# Atomwide_TwinMEMC.net
KiCad netlist of a schematic drawn in Altium Designer
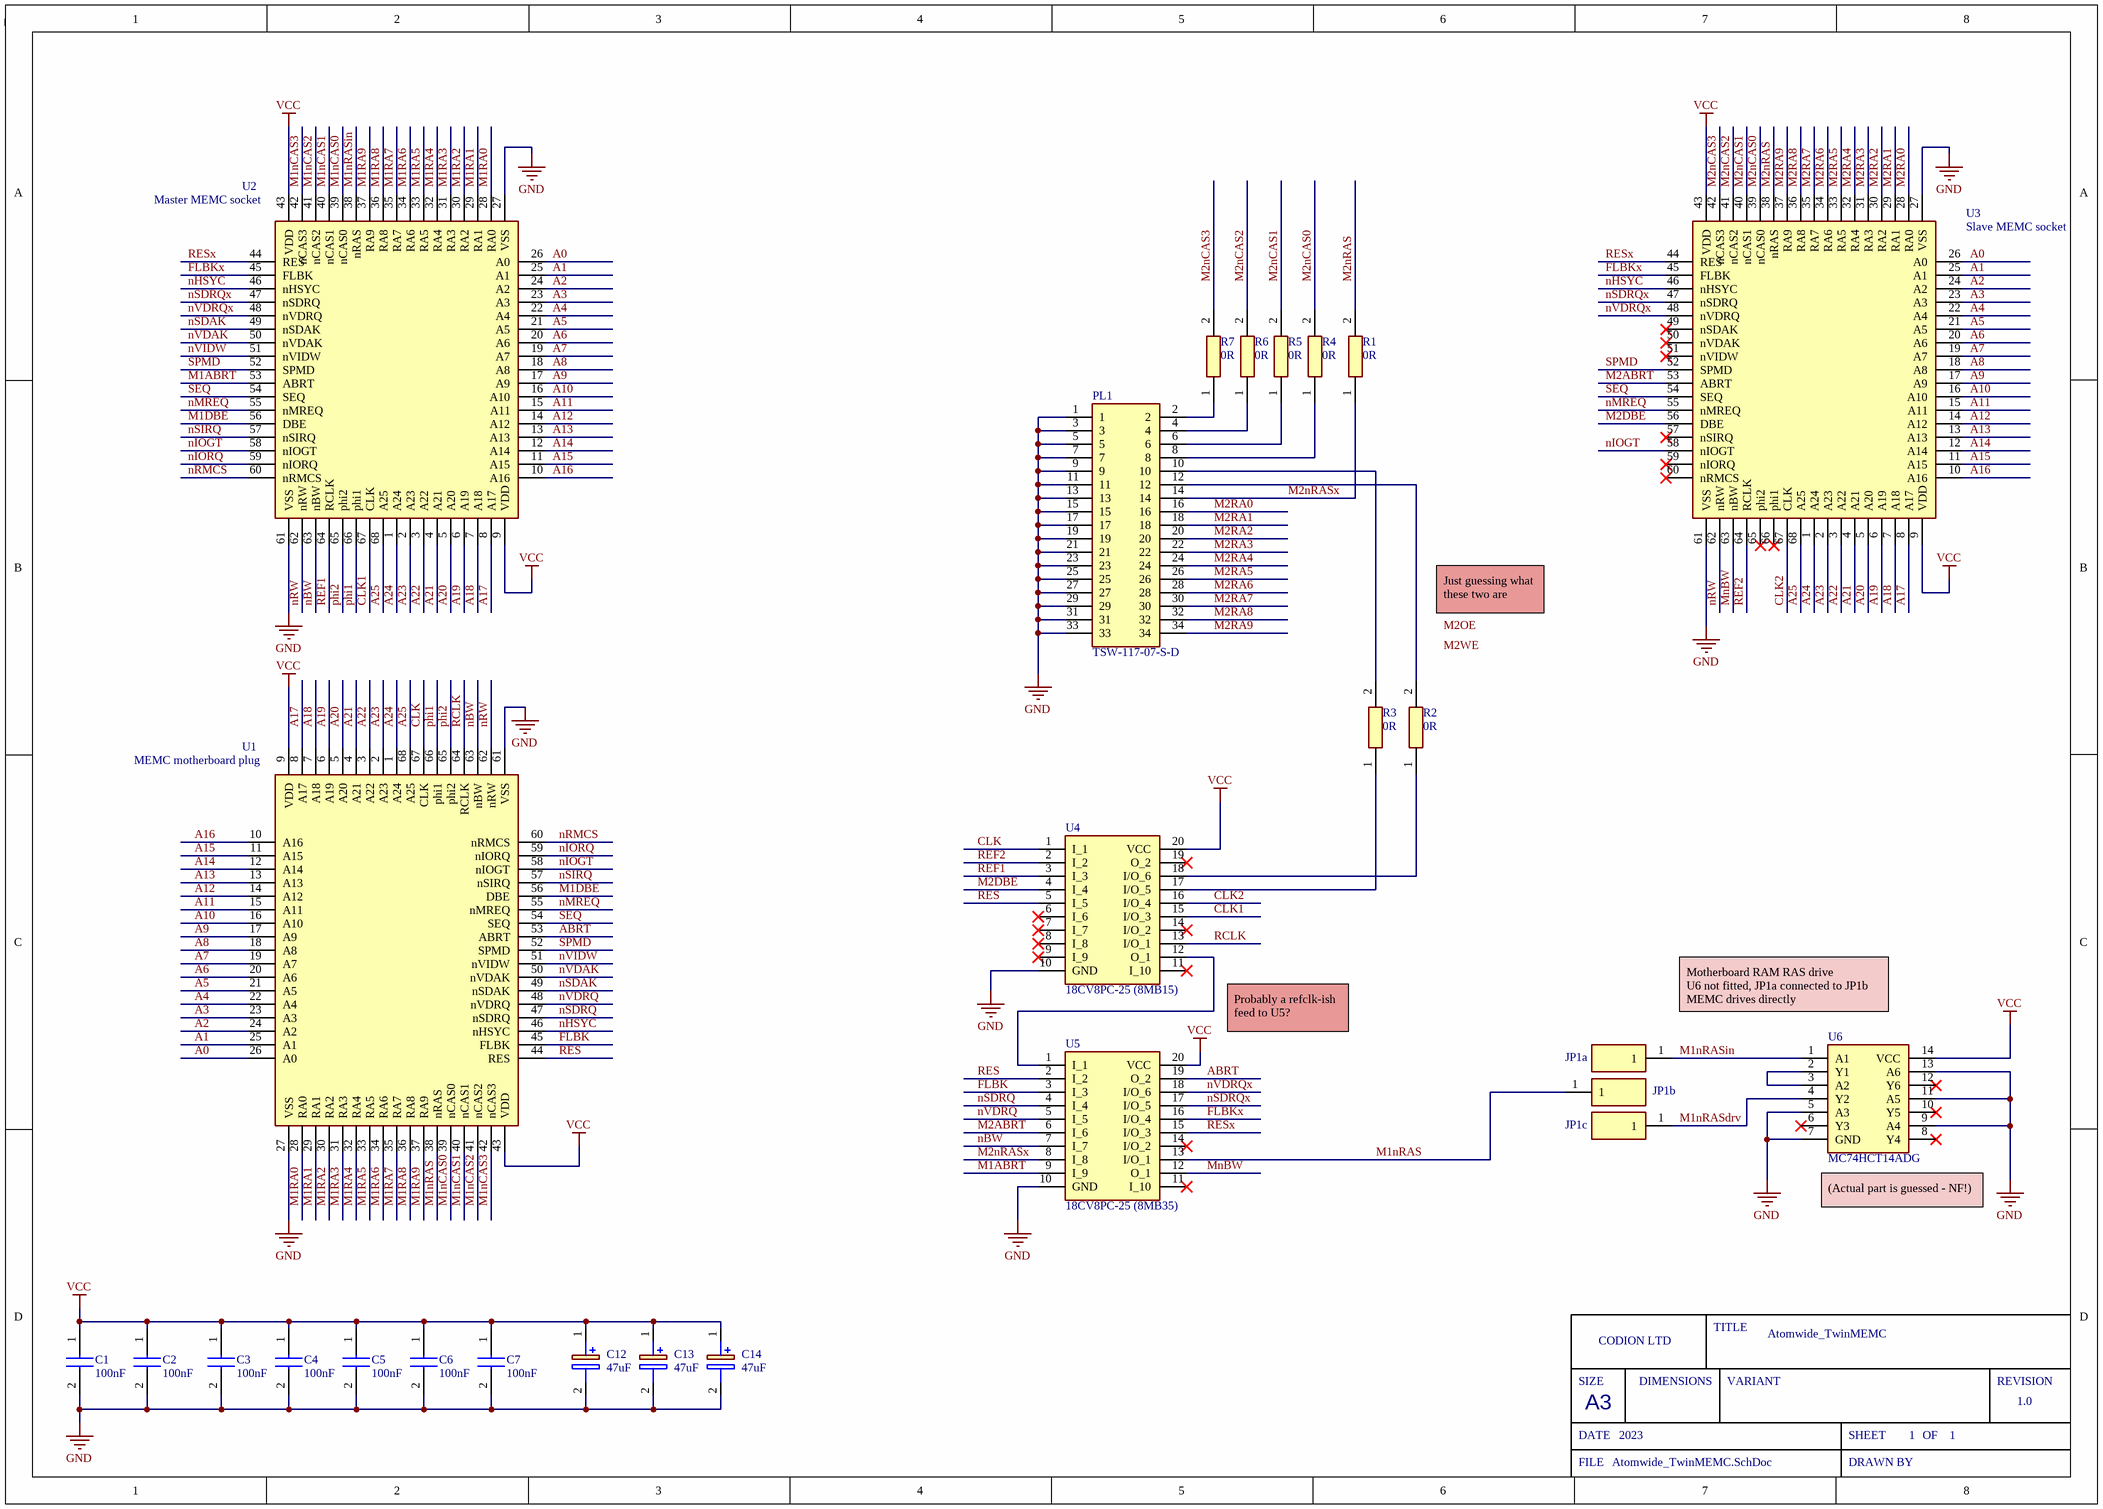
[diagram p0: Atomwide_TwinMEMC.SchDoc]

(export (version "E")
  (design (tool "Eeschema 10.0.6"))
  (components
    (comp (ref "C1")
      (value "100nF")
      (footprint "SamacSys:CAPC2012X145N")
      (description "Capacitor")
      (fields
        (field (name "MANUFACTURER_PART_NUMBER") "C2012X7R1H104K125AM")
        (field (name "MOUSER PART NUMBER") "810-C2012X7R1H104KT5")
      )
      (libsource (lib "*") (part "C2012X7R1H104K125AM"))
    )
    (comp (ref "C2")
      (value "100nF")
      (footprint "SamacSys:CAPC2012X145N")
      (description "Capacitor")
      (fields
        (field (name "MANUFACTURER_PART_NUMBER") "C2012X7R1H104K125AM")
        (field (name "MOUSER PART NUMBER") "810-C2012X7R1H104KT5")
      )
      (libsource (lib "*") (part "C2012X7R1H104K125AM"))
    )
    (comp (ref "C3")
      (value "100nF")
      (footprint "SamacSys:CAPC2012X145N")
      (description "Capacitor")
      (fields
        (field (name "MANUFACTURER_PART_NUMBER") "C2012X7R1H104K125AM")
        (field (name "MOUSER PART NUMBER") "810-C2012X7R1H104KT5")
      )
      (libsource (lib "*") (part "C2012X7R1H104K125AM"))
    )
    (comp (ref "C4")
      (value "100nF")
      (footprint "SamacSys:CAPC2012X145N")
      (description "Capacitor")
      (fields
        (field (name "MANUFACTURER_PART_NUMBER") "C2012X7R1H104K125AM")
        (field (name "MOUSER PART NUMBER") "810-C2012X7R1H104KT5")
      )
      (libsource (lib "*") (part "C2012X7R1H104K125AM"))
    )
    (comp (ref "C5")
      (value "100nF")
      (footprint "SamacSys:CAPC2012X145N")
      (description "Capacitor")
      (fields
        (field (name "MANUFACTURER_PART_NUMBER") "C2012X7R1H104K125AM")
        (field (name "MOUSER PART NUMBER") "810-C2012X7R1H104KT5")
      )
      (libsource (lib "*") (part "C2012X7R1H104K125AM"))
    )
    (comp (ref "C6")
      (value "100nF")
      (footprint "SamacSys:CAPC2012X145N")
      (description "Capacitor")
      (fields
        (field (name "MANUFACTURER_PART_NUMBER") "C2012X7R1H104K125AM")
        (field (name "MOUSER PART NUMBER") "810-C2012X7R1H104KT5")
      )
      (libsource (lib "*") (part "C2012X7R1H104K125AM"))
    )
    (comp (ref "C7")
      (value "100nF")
      (footprint "SamacSys:CAPC2012X145N")
      (description "Capacitor")
      (fields
        (field (name "MANUFACTURER_PART_NUMBER") "C2012X7R1H104K125AM")
        (field (name "MOUSER PART NUMBER") "810-C2012X7R1H104KT5")
      )
      (libsource (lib "*") (part "C2012X7R1H104K125AM"))
    )
    (comp (ref "C12")
      (value "47uF")
      (footprint "SamacSys:EEE1AA101SP")
      (description "Capacitor Polarised")
      (fields (field (name "MANUFACTURER_PART_NUMBER") "EEE1VA470WP"))
      (libsource (lib "*") (part "EEE1VA470WP"))
    )
    (comp (ref "C13")
      (value "47uF")
      (footprint "SamacSys:EEE1AA101SP")
      (description "Capacitor Polarised")
      (fields (field (name "MANUFACTURER_PART_NUMBER") "EEE1VA470WP"))
      (libsource (lib "*") (part "EEE1VA470WP"))
    )
    (comp (ref "C14")
      (value "47uF")
      (footprint "SamacSys:EEE1AA101SP")
      (description "Capacitor Polarised")
      (fields (field (name "MANUFACTURER_PART_NUMBER") "EEE1VA470WP"))
      (libsource (lib "*") (part "EEE1VA470WP"))
    )
    (comp (ref "JP1a")
      (value "~")
      (footprint "SamacSys:TSW-101-XX-YY-S")
      (description "Connector")
      (fields
        (field (name "MANUFACTURER_PART_NUMBER") "TSW-101-07-G-S")
        (field (name "MOUSER PART NUMBER") "200-TSW10107GS")
      )
      (libsource (lib "*") (part "TSW-101-07-G-S"))
    )
    (comp (ref "JP1b")
      (value "~")
      (footprint "SamacSys:TSW-101-XX-YY-S")
      (description "Connector")
      (fields
        (field (name "MANUFACTURER_PART_NUMBER") "TSW-101-07-G-S")
        (field (name "MOUSER PART NUMBER") "200-TSW10107GS")
      )
      (libsource (lib "") (part "TSW-101-07-G-S_1"))
    )
    (comp (ref "JP1c")
      (value "~")
      (footprint "SamacSys:TSW-101-XX-YY-S")
      (description "Connector")
      (fields
        (field (name "MANUFACTURER_PART_NUMBER") "TSW-101-07-G-S")
        (field (name "MOUSER PART NUMBER") "200-TSW10107GS")
      )
      (libsource (lib "*") (part "TSW-101-07-G-S"))
    )
    (comp (ref "PL1")
      (value "TSW-117-07-S-D")
      (footprint "SamacSys:TSW-117-XX-YY-D")
      (description "Connector")
      (fields (field (name "MOUSER PART NUMBER") "200-TSW11707SD"))
      (libsource (lib "*") (part "TSW-117-07-S-D"))
    )
    (comp (ref "R1")
      (value "0R")
      (footprint "SamacSys:RESC1005X40N")
      (description "Resistor")
      (fields
        (field (name "MANUFACTURER_PART_NUMBER") "CRCW040210K0FKEDHP")
        (field (name "MOUSER PART NUMBER") "71-CRCW040210K0FKEDH")
      )
      (libsource (lib "*") (part "CRCW040210K0FKEDHP"))
    )
    (comp (ref "R2")
      (value "0R")
      (footprint "SamacSys:RESC1005X40N")
      (description "Resistor")
      (fields
        (field (name "MANUFACTURER_PART_NUMBER") "CRCW040210K0FKEDHP")
        (field (name "MOUSER PART NUMBER") "71-CRCW040210K0FKEDH")
      )
      (libsource (lib "*") (part "CRCW040210K0FKEDHP"))
    )
    (comp (ref "R3")
      (value "0R")
      (footprint "SamacSys:RESC1005X40N")
      (description "Resistor")
      (fields
        (field (name "MANUFACTURER_PART_NUMBER") "CRCW040210K0FKEDHP")
        (field (name "MOUSER PART NUMBER") "71-CRCW040210K0FKEDH")
      )
      (libsource (lib "*") (part "CRCW040210K0FKEDHP"))
    )
    (comp (ref "R4")
      (value "0R")
      (footprint "SamacSys:RESC1005X40N")
      (description "Resistor")
      (fields
        (field (name "MANUFACTURER_PART_NUMBER") "CRCW040210K0FKEDHP")
        (field (name "MOUSER PART NUMBER") "71-CRCW040210K0FKEDH")
      )
      (libsource (lib "*") (part "CRCW040210K0FKEDHP"))
    )
    (comp (ref "R5")
      (value "0R")
      (footprint "SamacSys:RESC1005X40N")
      (description "Resistor")
      (fields
        (field (name "MANUFACTURER_PART_NUMBER") "CRCW040210K0FKEDHP")
        (field (name "MOUSER PART NUMBER") "71-CRCW040210K0FKEDH")
      )
      (libsource (lib "*") (part "CRCW040210K0FKEDHP"))
    )
    (comp (ref "R6")
      (value "0R")
      (footprint "SamacSys:RESC1005X40N")
      (description "Resistor")
      (fields
        (field (name "MANUFACTURER_PART_NUMBER") "CRCW040210K0FKEDHP")
        (field (name "MOUSER PART NUMBER") "71-CRCW040210K0FKEDH")
      )
      (libsource (lib "*") (part "CRCW040210K0FKEDHP"))
    )
    (comp (ref "R7")
      (value "0R")
      (footprint "SamacSys:RESC1005X40N")
      (description "Resistor")
      (fields
        (field (name "MANUFACTURER_PART_NUMBER") "CRCW040210K0FKEDHP")
        (field (name "MOUSER PART NUMBER") "71-CRCW040210K0FKEDH")
      )
      (libsource (lib "*") (part "CRCW040210K0FKEDHP"))
    )
    (comp (ref "U1")
      (value "MEMC motherboard plug")
      (footprint "MEMC_Plug")
      (description "MEMC plug")
      (libsource (lib "Acorn") (part "MEMC_Plug"))
    )
    (comp (ref "U2")
      (value "Master MEMC socket")
      (footprint "MEMC_Socket")
      (description "MEMC socket")
      (fields
        (field (name "MANUFACTURER_PART_NUMBER") "8468-21B1-RK-TR")
        (field (name "MOUSER PART NUMBER") "517-8468-21B1-RK-TR")
      )
      (libsource (lib "Acorn") (part "MEMC_Skt"))
    )
    (comp (ref "U3")
      (value "Slave MEMC socket")
      (footprint "MEMC_Socket")
      (description "MEMC socket")
      (fields
        (field (name "MANUFACTURER_PART_NUMBER") "8468-21B1-RK-TR")
        (field (name "MOUSER PART NUMBER") "517-8468-21B1-RK-TR")
      )
      (libsource (lib "Acorn") (part "MEMC_Skt"))
    )
    (comp (ref "U4")
      (value "18CV8PC-25 (8MB15)")
      (footprint "SamacSys:DIP762W66P254L2692H508Q20N")
      (description "Integrated Circuit")
      (fields
        (field (name "MANUFACTURER_PART_NUMBER") "PAL16R4AMJ")
        (field (name "MOUSER PART NUMBER") "595-PAL16R4AMJ")
      )
      (libsource (lib "*") (part "PAL16R4AMJ"))
    )
    (comp (ref "U5")
      (value "18CV8PC-25 (8MB35)")
      (footprint "SamacSys:DIP762W66P254L2692H508Q20N")
      (description "Integrated Circuit")
      (fields
        (field (name "MANUFACTURER_PART_NUMBER") "PAL16R4AMJ")
        (field (name "MOUSER PART NUMBER") "595-PAL16R4AMJ")
      )
      (libsource (lib "*") (part "PAL16R4AMJ"))
    )
    (comp (ref "U6")
      (value "MC74HCT14ADG")
      (footprint "SamacSys:SOIC127P600X175-14N")
      (description "Integrated Circuit")
      (fields (field (name "MOUSER PART NUMBER") "863-MC74HCT14ADG"))
      (libsource (lib "*") (part "MC74HCT14ADG"))
    )
  )
  (nets
    (net (code "1") (name "/A0") (class "Default")
      (node (ref "U1") (pin "26") (pinfunction "A0_26") (pintype "passive"))
      (node (ref "U2") (pin "26") (pinfunction "A0_26") (pintype "passive"))
      (node (ref "U3") (pin "26") (pinfunction "A0_26") (pintype "passive"))
    )
    (net (code "2") (name "/A1") (class "Default")
      (node (ref "U1") (pin "25") (pinfunction "A1_25") (pintype "passive"))
      (node (ref "U2") (pin "25") (pinfunction "A1_25") (pintype "passive"))
      (node (ref "U3") (pin "25") (pinfunction "A1_25") (pintype "passive"))
    )
    (net (code "3") (name "/A2") (class "Default")
      (node (ref "U1") (pin "24") (pinfunction "A2_24") (pintype "passive"))
      (node (ref "U2") (pin "24") (pinfunction "A2_24") (pintype "passive"))
      (node (ref "U3") (pin "24") (pinfunction "A2_24") (pintype "passive"))
    )
    (net (code "4") (name "/A3") (class "Default")
      (node (ref "U1") (pin "23") (pinfunction "A3_23") (pintype "passive"))
      (node (ref "U2") (pin "23") (pinfunction "A3_23") (pintype "passive"))
      (node (ref "U3") (pin "23") (pinfunction "A3_23") (pintype "passive"))
    )
    (net (code "5") (name "/A4") (class "Default")
      (node (ref "U1") (pin "22") (pinfunction "A4_22") (pintype "passive"))
      (node (ref "U2") (pin "22") (pinfunction "A4_22") (pintype "passive"))
      (node (ref "U3") (pin "22") (pinfunction "A4_22") (pintype "passive"))
    )
    (net (code "6") (name "/A5") (class "Default")
      (node (ref "U1") (pin "21") (pinfunction "A5_21") (pintype "passive"))
      (node (ref "U2") (pin "21") (pinfunction "A5_21") (pintype "passive"))
      (node (ref "U3") (pin "21") (pinfunction "A5_21") (pintype "passive"))
    )
    (net (code "7") (name "/A6") (class "Default")
      (node (ref "U1") (pin "20") (pinfunction "A6_20") (pintype "passive"))
      (node (ref "U2") (pin "20") (pinfunction "A6_20") (pintype "passive"))
      (node (ref "U3") (pin "20") (pinfunction "A6_20") (pintype "passive"))
    )
    (net (code "8") (name "/A7") (class "Default")
      (node (ref "U1") (pin "19") (pinfunction "A7_19") (pintype "passive"))
      (node (ref "U2") (pin "19") (pinfunction "A7_19") (pintype "passive"))
      (node (ref "U3") (pin "19") (pinfunction "A7_19") (pintype "passive"))
    )
    (net (code "9") (name "/A8") (class "Default")
      (node (ref "U1") (pin "18") (pinfunction "A8_18") (pintype "passive"))
      (node (ref "U2") (pin "18") (pinfunction "A8_18") (pintype "passive"))
      (node (ref "U3") (pin "18") (pinfunction "A8_18") (pintype "passive"))
    )
    (net (code "10") (name "/A9") (class "Default")
      (node (ref "U1") (pin "17") (pinfunction "A9_17") (pintype "passive"))
      (node (ref "U2") (pin "17") (pinfunction "A9_17") (pintype "passive"))
      (node (ref "U3") (pin "17") (pinfunction "A9_17") (pintype "passive"))
    )
    (net (code "11") (name "/A10") (class "Default")
      (node (ref "U1") (pin "16") (pinfunction "A10_16") (pintype "passive"))
      (node (ref "U2") (pin "16") (pinfunction "A10_16") (pintype "passive"))
      (node (ref "U3") (pin "16") (pinfunction "A10_16") (pintype "passive"))
    )
    (net (code "12") (name "/A11") (class "Default")
      (node (ref "U1") (pin "15") (pinfunction "A11_15") (pintype "passive"))
      (node (ref "U2") (pin "15") (pinfunction "A11_15") (pintype "passive"))
      (node (ref "U3") (pin "15") (pinfunction "A11_15") (pintype "passive"))
    )
    (net (code "13") (name "/A12") (class "Default")
      (node (ref "U1") (pin "14") (pinfunction "A12_14") (pintype "passive"))
      (node (ref "U2") (pin "14") (pinfunction "A12_14") (pintype "passive"))
      (node (ref "U3") (pin "14") (pinfunction "A12_14") (pintype "passive"))
    )
    (net (code "14") (name "/A13") (class "Default")
      (node (ref "U1") (pin "13") (pinfunction "A13_13") (pintype "passive"))
      (node (ref "U2") (pin "13") (pinfunction "A13_13") (pintype "passive"))
      (node (ref "U3") (pin "13") (pinfunction "A13_13") (pintype "passive"))
    )
    (net (code "15") (name "/A14") (class "Default")
      (node (ref "U1") (pin "12") (pinfunction "A14_12") (pintype "passive"))
      (node (ref "U2") (pin "12") (pinfunction "A14_12") (pintype "passive"))
      (node (ref "U3") (pin "12") (pinfunction "A14_12") (pintype "passive"))
    )
    (net (code "16") (name "/A15") (class "Default")
      (node (ref "U1") (pin "11") (pinfunction "A15_11") (pintype "passive"))
      (node (ref "U2") (pin "11") (pinfunction "A15_11") (pintype "passive"))
      (node (ref "U3") (pin "11") (pinfunction "A15_11") (pintype "passive"))
    )
    (net (code "17") (name "/A16") (class "Default")
      (node (ref "U1") (pin "10") (pinfunction "A16_10") (pintype "passive"))
      (node (ref "U2") (pin "10") (pinfunction "A16_10") (pintype "passive"))
      (node (ref "U3") (pin "10") (pinfunction "A16_10") (pintype "passive"))
    )
    (net (code "18") (name "/A17") (class "Default")
      (node (ref "U1") (pin "8") (pinfunction "A17_8") (pintype "passive"))
      (node (ref "U2") (pin "8") (pinfunction "A17_8") (pintype "passive"))
      (node (ref "U3") (pin "8") (pinfunction "A17_8") (pintype "passive"))
    )
    (net (code "19") (name "/A18") (class "Default")
      (node (ref "U1") (pin "7") (pinfunction "A18_7") (pintype "passive"))
      (node (ref "U2") (pin "7") (pinfunction "A18_7") (pintype "passive"))
      (node (ref "U3") (pin "7") (pinfunction "A18_7") (pintype "passive"))
    )
    (net (code "20") (name "/A19") (class "Default")
      (node (ref "U1") (pin "6") (pinfunction "A19_6") (pintype "passive"))
      (node (ref "U2") (pin "6") (pinfunction "A19_6") (pintype "passive"))
      (node (ref "U3") (pin "6") (pinfunction "A19_6") (pintype "passive"))
    )
    (net (code "21") (name "/A20") (class "Default")
      (node (ref "U1") (pin "5") (pinfunction "A20_5") (pintype "passive"))
      (node (ref "U2") (pin "5") (pinfunction "A20_5") (pintype "passive"))
      (node (ref "U3") (pin "5") (pinfunction "A20_5") (pintype "passive"))
    )
    (net (code "22") (name "/A21") (class "Default")
      (node (ref "U1") (pin "4") (pinfunction "A21_4") (pintype "passive"))
      (node (ref "U2") (pin "4") (pinfunction "A21_4") (pintype "passive"))
      (node (ref "U3") (pin "4") (pinfunction "A21_4") (pintype "passive"))
    )
    (net (code "23") (name "/A22") (class "Default")
      (node (ref "U1") (pin "3") (pinfunction "A22_3") (pintype "passive"))
      (node (ref "U2") (pin "3") (pinfunction "A22_3") (pintype "passive"))
      (node (ref "U3") (pin "3") (pinfunction "A22_3") (pintype "passive"))
    )
    (net (code "24") (name "/A23") (class "Default")
      (node (ref "U1") (pin "2") (pinfunction "A23_2") (pintype "passive"))
      (node (ref "U2") (pin "2") (pinfunction "A23_2") (pintype "passive"))
      (node (ref "U3") (pin "2") (pinfunction "A23_2") (pintype "passive"))
    )
    (net (code "25") (name "/A24") (class "Default")
      (node (ref "U1") (pin "1") (pinfunction "A24_1") (pintype "passive"))
      (node (ref "U2") (pin "1") (pinfunction "A24_1") (pintype "passive"))
      (node (ref "U3") (pin "1") (pinfunction "A24_1") (pintype "passive"))
    )
    (net (code "26") (name "/A25") (class "Default")
      (node (ref "U1") (pin "68") (pinfunction "A25_68") (pintype "passive"))
      (node (ref "U2") (pin "68") (pinfunction "A25_68") (pintype "passive"))
      (node (ref "U3") (pin "68") (pinfunction "A25_68") (pintype "passive"))
    )
    (net (code "27") (name "/ABRT") (class "Default")
      (node (ref "U1") (pin "53") (pinfunction "ABRT_53") (pintype "passive"))
      (node (ref "U5") (pin "19") (pinfunction "O_2_19") (pintype "passive"))
    )
    (net (code "28") (name "/CLK") (class "Default")
      (node (ref "U1") (pin "67") (pinfunction "CLK_67") (pintype "passive"))
      (node (ref "U4") (pin "1") (pinfunction "I_1_1") (pintype "passive"))
    )
    (net (code "29") (name "/CLK1") (class "Default")
      (node (ref "U2") (pin "67") (pinfunction "CLK_67") (pintype "passive"))
      (node (ref "U4") (pin "15") (pinfunction "I/O_3_15") (pintype "passive"))
    )
    (net (code "30") (name "/CLK2") (class "Default")
      (node (ref "U3") (pin "67") (pinfunction "CLK_67") (pintype "passive"))
      (node (ref "U4") (pin "16") (pinfunction "I/O_4_16") (pintype "passive"))
    )
    (net (code "31") (name "/FLBK") (class "Default")
      (node (ref "U1") (pin "45") (pinfunction "FLBK_45") (pintype "passive"))
      (node (ref "U5") (pin "3") (pinfunction "I_3_3") (pintype "passive"))
    )
    (net (code "32") (name "/FLBKx") (class "Default")
      (node (ref "U2") (pin "45") (pinfunction "FLBK_45") (pintype "passive"))
      (node (ref "U3") (pin "45") (pinfunction "FLBK_45") (pintype "passive"))
      (node (ref "U5") (pin "16") (pinfunction "I/O_4_16") (pintype "passive"))
    )
    (net (code "33") (name "/M1ABRT") (class "Default")
      (node (ref "U2") (pin "53") (pinfunction "ABRT_53") (pintype "passive"))
      (node (ref "U5") (pin "9") (pinfunction "I_9_9") (pintype "passive"))
    )
    (net (code "34") (name "/M1DBE") (class "Default")
      (node (ref "U1") (pin "56") (pinfunction "DBE_56") (pintype "passive"))
      (node (ref "U2") (pin "56") (pinfunction "DBE_56") (pintype "passive"))
    )
    (net (code "35") (name "/M1RA0") (class "Default")
      (node (ref "U1") (pin "28") (pinfunction "RA0_28") (pintype "passive"))
      (node (ref "U2") (pin "28") (pinfunction "RA0_28") (pintype "passive"))
    )
    (net (code "36") (name "/M1RA1") (class "Default")
      (node (ref "U1") (pin "29") (pinfunction "RA1_29") (pintype "passive"))
      (node (ref "U2") (pin "29") (pinfunction "RA1_29") (pintype "passive"))
    )
    (net (code "37") (name "/M1RA2") (class "Default")
      (node (ref "U1") (pin "30") (pinfunction "RA2_30") (pintype "passive"))
      (node (ref "U2") (pin "30") (pinfunction "RA2_30") (pintype "passive"))
    )
    (net (code "38") (name "/M1RA3") (class "Default")
      (node (ref "U1") (pin "31") (pinfunction "RA3_31") (pintype "passive"))
      (node (ref "U2") (pin "31") (pinfunction "RA3_31") (pintype "passive"))
    )
    (net (code "39") (name "/M1RA4") (class "Default")
      (node (ref "U1") (pin "32") (pinfunction "RA4_32") (pintype "passive"))
      (node (ref "U2") (pin "32") (pinfunction "RA4_32") (pintype "passive"))
    )
    (net (code "40") (name "/M1RA5") (class "Default")
      (node (ref "U1") (pin "33") (pinfunction "RA5_33") (pintype "passive"))
      (node (ref "U2") (pin "33") (pinfunction "RA5_33") (pintype "passive"))
    )
    (net (code "41") (name "/M1RA6") (class "Default")
      (node (ref "U1") (pin "34") (pinfunction "RA6_34") (pintype "passive"))
      (node (ref "U2") (pin "34") (pinfunction "RA6_34") (pintype "passive"))
    )
    (net (code "42") (name "/M1RA7") (class "Default")
      (node (ref "U1") (pin "35") (pinfunction "RA7_35") (pintype "passive"))
      (node (ref "U2") (pin "35") (pinfunction "RA7_35") (pintype "passive"))
    )
    (net (code "43") (name "/M1RA8") (class "Default")
      (node (ref "U1") (pin "36") (pinfunction "RA8_36") (pintype "passive"))
      (node (ref "U2") (pin "36") (pinfunction "RA8_36") (pintype "passive"))
    )
    (net (code "44") (name "/M1RA9") (class "Default")
      (node (ref "U1") (pin "37") (pinfunction "RA9_37") (pintype "passive"))
      (node (ref "U2") (pin "37") (pinfunction "RA9_37") (pintype "passive"))
    )
    (net (code "45") (name "/M1nCAS0") (class "Default")
      (node (ref "U1") (pin "39") (pinfunction "nCAS0_39") (pintype "passive"))
      (node (ref "U2") (pin "39") (pinfunction "nCAS0_39") (pintype "passive"))
    )
    (net (code "46") (name "/M1nCAS1") (class "Default")
      (node (ref "U1") (pin "40") (pinfunction "nCAS1_40") (pintype "passive"))
      (node (ref "U2") (pin "40") (pinfunction "nCAS1_40") (pintype "passive"))
    )
    (net (code "47") (name "/M1nCAS2") (class "Default")
      (node (ref "U1") (pin "41") (pinfunction "nCAS2_41") (pintype "passive"))
      (node (ref "U2") (pin "41") (pinfunction "nCAS2_41") (pintype "passive"))
    )
    (net (code "48") (name "/M1nCAS3") (class "Default")
      (node (ref "U1") (pin "42") (pinfunction "nCAS3_42") (pintype "passive"))
      (node (ref "U2") (pin "42") (pinfunction "nCAS3_42") (pintype "passive"))
    )
    (net (code "49") (name "/M1nRAS") (class "Default")
      (node (ref "JP1b") (pin "1") (pinfunction "1_1") (pintype "passive"))
      (node (ref "U1") (pin "38") (pinfunction "nRAS_38") (pintype "passive"))
      (node (ref "U5") (pin "13") (pinfunction "I/O_1_13") (pintype "passive"))
    )
    (net (code "50") (name "/M1nRASdrv") (class "Default")
      (node (ref "JP1c") (pin "1") (pinfunction "1_1") (pintype "passive"))
      (node (ref "U6") (pin "4") (pinfunction "Y2_4") (pintype "passive"))
    )
    (net (code "51") (name "/M1nRASin") (class "Default")
      (node (ref "JP1a") (pin "1") (pinfunction "1_1") (pintype "passive"))
      (node (ref "U2") (pin "38") (pinfunction "nRAS_38") (pintype "passive"))
      (node (ref "U6") (pin "1") (pinfunction "A1_1") (pintype "passive"))
    )
    (net (code "52") (name "/M2ABRT") (class "Default")
      (node (ref "U3") (pin "53") (pinfunction "ABRT_53") (pintype "passive"))
      (node (ref "U5") (pin "6") (pinfunction "I_6_6") (pintype "passive"))
    )
    (net (code "53") (name "/M2DBE") (class "Default")
      (node (ref "U3") (pin "56") (pinfunction "DBE_56") (pintype "passive"))
      (node (ref "U4") (pin "4") (pinfunction "I_4_4") (pintype "passive"))
    )
    (net (code "55") (name "/M2RA0") (class "Default")
      (node (ref "PL1") (pin "16") (pinfunction "16_16") (pintype "passive"))
      (node (ref "U3") (pin "28") (pinfunction "RA0_28") (pintype "passive"))
    )
    (net (code "56") (name "/M2RA1") (class "Default")
      (node (ref "PL1") (pin "18") (pinfunction "18_18") (pintype "passive"))
      (node (ref "U3") (pin "29") (pinfunction "RA1_29") (pintype "passive"))
    )
    (net (code "57") (name "/M2RA2") (class "Default")
      (node (ref "PL1") (pin "20") (pinfunction "20_20") (pintype "passive"))
      (node (ref "U3") (pin "30") (pinfunction "RA2_30") (pintype "passive"))
    )
    (net (code "58") (name "/M2RA3") (class "Default")
      (node (ref "PL1") (pin "22") (pinfunction "22_22") (pintype "passive"))
      (node (ref "U3") (pin "31") (pinfunction "RA3_31") (pintype "passive"))
    )
    (net (code "59") (name "/M2RA4") (class "Default")
      (node (ref "PL1") (pin "24") (pinfunction "24_24") (pintype "passive"))
      (node (ref "U3") (pin "32") (pinfunction "RA4_32") (pintype "passive"))
    )
    (net (code "60") (name "/M2RA5") (class "Default")
      (node (ref "PL1") (pin "26") (pinfunction "26_26") (pintype "passive"))
      (node (ref "U3") (pin "33") (pinfunction "RA5_33") (pintype "passive"))
    )
    (net (code "61") (name "/M2RA6") (class "Default")
      (node (ref "PL1") (pin "28") (pinfunction "28_28") (pintype "passive"))
      (node (ref "U3") (pin "34") (pinfunction "RA6_34") (pintype "passive"))
    )
    (net (code "62") (name "/M2RA7") (class "Default")
      (node (ref "PL1") (pin "30") (pinfunction "30_30") (pintype "passive"))
      (node (ref "U3") (pin "35") (pinfunction "RA7_35") (pintype "passive"))
    )
    (net (code "63") (name "/M2RA8") (class "Default")
      (node (ref "PL1") (pin "32") (pinfunction "32_32") (pintype "passive"))
      (node (ref "U3") (pin "36") (pinfunction "RA8_36") (pintype "passive"))
    )
    (net (code "64") (name "/M2RA9") (class "Default")
      (node (ref "PL1") (pin "34") (pinfunction "34_34") (pintype "passive"))
      (node (ref "U3") (pin "37") (pinfunction "RA9_37") (pintype "passive"))
    )
    (net (code "66") (name "/M2nCAS0") (class "Default")
      (node (ref "R4") (pin "2") (pinfunction "2_2") (pintype "passive"))
      (node (ref "U3") (pin "39") (pinfunction "nCAS0_39") (pintype "passive"))
    )
    (net (code "67") (name "/M2nCAS1") (class "Default")
      (node (ref "R5") (pin "2") (pinfunction "2_2") (pintype "passive"))
      (node (ref "U3") (pin "40") (pinfunction "nCAS1_40") (pintype "passive"))
    )
    (net (code "68") (name "/M2nCAS2") (class "Default")
      (node (ref "R6") (pin "2") (pinfunction "2_2") (pintype "passive"))
      (node (ref "U3") (pin "41") (pinfunction "nCAS2_41") (pintype "passive"))
    )
    (net (code "69") (name "/M2nCAS3") (class "Default")
      (node (ref "R7") (pin "2") (pinfunction "2_2") (pintype "passive"))
      (node (ref "U3") (pin "42") (pinfunction "nCAS3_42") (pintype "passive"))
    )
    (net (code "70") (name "/M2nRAS") (class "Default")
      (node (ref "R1") (pin "2") (pinfunction "2_2") (pintype "passive"))
      (node (ref "U3") (pin "38") (pinfunction "nRAS_38") (pintype "passive"))
    )
    (net (code "71") (name "/M2nRASx") (class "Default")
      (node (ref "PL1") (pin "14") (pinfunction "14_14") (pintype "passive"))
      (node (ref "R1") (pin "1") (pinfunction "1_1") (pintype "passive"))
      (node (ref "U5") (pin "8") (pinfunction "I_8_8") (pintype "passive"))
    )
    (net (code "72") (name "/MnBW") (class "Default")
      (node (ref "U3") (pin "63") (pinfunction "nBW_63") (pintype "passive"))
      (node (ref "U5") (pin "12") (pinfunction "O_1_12") (pintype "passive"))
    )
    (net (code "73") (name "/RCLK") (class "Default")
      (node (ref "U1") (pin "64") (pinfunction "RCLK_64") (pintype "passive"))
      (node (ref "U4") (pin "13") (pinfunction "I/O_1_13") (pintype "passive"))
    )
    (net (code "74") (name "/REF1") (class "Default")
      (node (ref "U2") (pin "64") (pinfunction "RCLK_64") (pintype "passive"))
      (node (ref "U4") (pin "3") (pinfunction "I_3_3") (pintype "passive"))
    )
    (net (code "75") (name "/REF2") (class "Default")
      (node (ref "U3") (pin "64") (pinfunction "RCLK_64") (pintype "passive"))
      (node (ref "U4") (pin "2") (pinfunction "I_2_2") (pintype "passive"))
    )
    (net (code "76") (name "/RES") (class "Default")
      (node (ref "U1") (pin "44") (pinfunction "RES_44") (pintype "passive"))
      (node (ref "U4") (pin "5") (pinfunction "I_5_5") (pintype "passive"))
      (node (ref "U5") (pin "2") (pinfunction "I_2_2") (pintype "passive"))
    )
    (net (code "77") (name "/RESx") (class "Default")
      (node (ref "U2") (pin "44") (pinfunction "RES_44") (pintype "passive"))
      (node (ref "U3") (pin "44") (pinfunction "RES_44") (pintype "passive"))
      (node (ref "U5") (pin "15") (pinfunction "I/O_3_15") (pintype "passive"))
    )
    (net (code "78") (name "/SEQ") (class "Default")
      (node (ref "U1") (pin "54") (pinfunction "SEQ_54") (pintype "passive"))
      (node (ref "U2") (pin "54") (pinfunction "SEQ_54") (pintype "passive"))
      (node (ref "U3") (pin "54") (pinfunction "SEQ_54") (pintype "passive"))
    )
    (net (code "79") (name "/SPMD") (class "Default")
      (node (ref "U1") (pin "52") (pinfunction "SPMD_52") (pintype "passive"))
      (node (ref "U2") (pin "52") (pinfunction "SPMD_52") (pintype "passive"))
      (node (ref "U3") (pin "52") (pinfunction "SPMD_52") (pintype "passive"))
    )
    (net (code "80") (name "/nBW") (class "Default")
      (node (ref "U1") (pin "63") (pinfunction "nBW_63") (pintype "passive"))
      (node (ref "U2") (pin "63") (pinfunction "nBW_63") (pintype "passive"))
      (node (ref "U5") (pin "7") (pinfunction "I_7_7") (pintype "passive"))
    )
    (net (code "81") (name "/nHSYC") (class "Default")
      (node (ref "U1") (pin "46") (pinfunction "nHSYC_46") (pintype "passive"))
      (node (ref "U2") (pin "46") (pinfunction "nHSYC_46") (pintype "passive"))
      (node (ref "U3") (pin "46") (pinfunction "nHSYC_46") (pintype "passive"))
    )
    (net (code "82") (name "/nIOGT") (class "Default")
      (node (ref "U1") (pin "58") (pinfunction "nIOGT_58") (pintype "passive"))
      (node (ref "U2") (pin "58") (pinfunction "nIOGT_58") (pintype "passive"))
      (node (ref "U3") (pin "58") (pinfunction "nIOGT_58") (pintype "passive"))
    )
    (net (code "83") (name "/nIORQ") (class "Default")
      (node (ref "U1") (pin "59") (pinfunction "nIORQ_59") (pintype "passive"))
      (node (ref "U2") (pin "59") (pinfunction "nIORQ_59") (pintype "passive"))
    )
    (net (code "84") (name "/nMREQ") (class "Default")
      (node (ref "U1") (pin "55") (pinfunction "nMREQ_55") (pintype "passive"))
      (node (ref "U2") (pin "55") (pinfunction "nMREQ_55") (pintype "passive"))
      (node (ref "U3") (pin "55") (pinfunction "nMREQ_55") (pintype "passive"))
    )
    (net (code "85") (name "/nRMCS") (class "Default")
      (node (ref "U1") (pin "60") (pinfunction "nRMCS_60") (pintype "passive"))
      (node (ref "U2") (pin "60") (pinfunction "nRMCS_60") (pintype "passive"))
    )
    (net (code "86") (name "/nRW") (class "Default")
      (node (ref "U1") (pin "62") (pinfunction "nRW_62") (pintype "passive"))
      (node (ref "U2") (pin "62") (pinfunction "nRW_62") (pintype "passive"))
      (node (ref "U3") (pin "62") (pinfunction "nRW_62") (pintype "passive"))
    )
    (net (code "87") (name "/nSDAK") (class "Default")
      (node (ref "U1") (pin "49") (pinfunction "nSDAK_49") (pintype "passive"))
      (node (ref "U2") (pin "49") (pinfunction "nSDAK_49") (pintype "passive"))
    )
    (net (code "88") (name "/nSDRQ") (class "Default")
      (node (ref "U1") (pin "47") (pinfunction "nSDRQ_47") (pintype "passive"))
      (node (ref "U5") (pin "4") (pinfunction "I_4_4") (pintype "passive"))
    )
    (net (code "89") (name "/nSDRQx") (class "Default")
      (node (ref "U2") (pin "47") (pinfunction "nSDRQ_47") (pintype "passive"))
      (node (ref "U3") (pin "47") (pinfunction "nSDRQ_47") (pintype "passive"))
      (node (ref "U5") (pin "17") (pinfunction "I/O_5_17") (pintype "passive"))
    )
    (net (code "90") (name "/nSIRQ") (class "Default")
      (node (ref "U1") (pin "57") (pinfunction "nSIRQ_57") (pintype "passive"))
      (node (ref "U2") (pin "57") (pinfunction "nSIRQ_57") (pintype "passive"))
    )
    (net (code "91") (name "/nVDAK") (class "Default")
      (node (ref "U1") (pin "50") (pinfunction "nVDAK_50") (pintype "passive"))
      (node (ref "U2") (pin "50") (pinfunction "nVDAK_50") (pintype "passive"))
    )
    (net (code "92") (name "/nVDRQ") (class "Default")
      (node (ref "U1") (pin "48") (pinfunction "nVDRQ_48") (pintype "passive"))
      (node (ref "U5") (pin "5") (pinfunction "I_5_5") (pintype "passive"))
    )
    (net (code "93") (name "/nVDRQx") (class "Default")
      (node (ref "U2") (pin "48") (pinfunction "nVDRQ_48") (pintype "passive"))
      (node (ref "U3") (pin "48") (pinfunction "nVDRQ_48") (pintype "passive"))
      (node (ref "U5") (pin "18") (pinfunction "I/O_6_18") (pintype "passive"))
    )
    (net (code "94") (name "/nVIDW") (class "Default")
      (node (ref "U1") (pin "51") (pinfunction "nVIDW_51") (pintype "passive"))
      (node (ref "U2") (pin "51") (pinfunction "nVIDW_51") (pintype "passive"))
    )
    (net (code "95") (name "/phi1") (class "Default")
      (node (ref "U1") (pin "66") (pinfunction "phi1_66") (pintype "passive"))
      (node (ref "U2") (pin "66") (pinfunction "phi1_66") (pintype "passive"))
    )
    (net (code "96") (name "/phi2") (class "Default")
      (node (ref "U1") (pin "65") (pinfunction "phi2_65") (pintype "passive"))
      (node (ref "U2") (pin "65") (pinfunction "phi2_65") (pintype "passive"))
    )
    (net (code "97") (name "GND") (class "Default")
      (node (ref "C1") (pin "2") (pinfunction "2_2") (pintype "passive"))
      (node (ref "C12") (pin "2") (pinfunction "-_2") (pintype "passive"))
      (node (ref "C13") (pin "2") (pinfunction "-_2") (pintype "passive"))
      (node (ref "C14") (pin "2") (pinfunction "-_2") (pintype "passive"))
      (node (ref "C2") (pin "2") (pinfunction "2_2") (pintype "passive"))
      (node (ref "C3") (pin "2") (pinfunction "2_2") (pintype "passive"))
      (node (ref "C4") (pin "2") (pinfunction "2_2") (pintype "passive"))
      (node (ref "C5") (pin "2") (pinfunction "2_2") (pintype "passive"))
      (node (ref "C6") (pin "2") (pinfunction "2_2") (pintype "passive"))
      (node (ref "C7") (pin "2") (pinfunction "2_2") (pintype "passive"))
      (node (ref "PL1") (pin "1") (pinfunction "1_1") (pintype "passive"))
      (node (ref "PL1") (pin "11") (pinfunction "11_11") (pintype "passive"))
      (node (ref "PL1") (pin "13") (pinfunction "13_13") (pintype "passive"))
      (node (ref "PL1") (pin "15") (pinfunction "15_15") (pintype "passive"))
      (node (ref "PL1") (pin "17") (pinfunction "17_17") (pintype "passive"))
      (node (ref "PL1") (pin "19") (pinfunction "19_19") (pintype "passive"))
      (node (ref "PL1") (pin "21") (pinfunction "21_21") (pintype "passive"))
      (node (ref "PL1") (pin "23") (pinfunction "23_23") (pintype "passive"))
      (node (ref "PL1") (pin "25") (pinfunction "25_25") (pintype "passive"))
      (node (ref "PL1") (pin "27") (pinfunction "27_27") (pintype "passive"))
      (node (ref "PL1") (pin "29") (pinfunction "29_29") (pintype "passive"))
      (node (ref "PL1") (pin "3") (pinfunction "3_3") (pintype "passive"))
      (node (ref "PL1") (pin "31") (pinfunction "31_31") (pintype "passive"))
      (node (ref "PL1") (pin "33") (pinfunction "33_33") (pintype "passive"))
      (node (ref "PL1") (pin "5") (pinfunction "5_5") (pintype "passive"))
      (node (ref "PL1") (pin "7") (pinfunction "7_7") (pintype "passive"))
      (node (ref "PL1") (pin "9") (pinfunction "9_9") (pintype "passive"))
      (node (ref "U1") (pin "27") (pinfunction "VSS_27") (pintype "passive"))
      (node (ref "U1") (pin "61") (pinfunction "VSS_61") (pintype "passive"))
      (node (ref "U2") (pin "27") (pinfunction "VSS_27") (pintype "passive"))
      (node (ref "U2") (pin "61") (pinfunction "VSS_61") (pintype "passive"))
      (node (ref "U3") (pin "27") (pinfunction "VSS_27") (pintype "passive"))
      (node (ref "U3") (pin "61") (pinfunction "VSS_61") (pintype "passive"))
      (node (ref "U4") (pin "10") (pinfunction "GND_10") (pintype "passive"))
      (node (ref "U5") (pin "10") (pinfunction "GND_10") (pintype "passive"))
      (node (ref "U6") (pin "11") (pinfunction "A5_11") (pintype "passive"))
      (node (ref "U6") (pin "13") (pinfunction "A6_13") (pintype "passive"))
      (node (ref "U6") (pin "5") (pinfunction "A3_5") (pintype "passive"))
      (node (ref "U6") (pin "7") (pinfunction "GND_7") (pintype "passive"))
      (node (ref "U6") (pin "9") (pinfunction "A4_9") (pintype "passive"))
    )
    (net (code "98") (name "Net-(PL1-Pad2)") (class "Default")
      (node (ref "PL1") (pin "2") (pinfunction "2_2") (pintype "passive"))
      (node (ref "R7") (pin "1") (pinfunction "1_1") (pintype "passive"))
    )
    (net (code "99") (name "Net-(PL1-Pad4)") (class "Default")
      (node (ref "PL1") (pin "4") (pinfunction "4_4") (pintype "passive"))
      (node (ref "R6") (pin "1") (pinfunction "1_1") (pintype "passive"))
    )
    (net (code "100") (name "Net-(PL1-Pad6)") (class "Default")
      (node (ref "PL1") (pin "6") (pinfunction "6_6") (pintype "passive"))
      (node (ref "R5") (pin "1") (pinfunction "1_1") (pintype "passive"))
    )
    (net (code "101") (name "Net-(PL1-Pad8)") (class "Default")
      (node (ref "PL1") (pin "8") (pinfunction "8_8") (pintype "passive"))
      (node (ref "R4") (pin "1") (pinfunction "1_1") (pintype "passive"))
    )
    (net (code "102") (name "Net-(PL1-Pad10)") (class "Default")
      (node (ref "PL1") (pin "10") (pinfunction "10_10") (pintype "passive"))
      (node (ref "R3") (pin "2") (pinfunction "2_2") (pintype "passive"))
    )
    (net (code "103") (name "Net-(PL1-Pad12)") (class "Default")
      (node (ref "PL1") (pin "12") (pinfunction "12_12") (pintype "passive"))
      (node (ref "R2") (pin "2") (pinfunction "2_2") (pintype "passive"))
    )
    (net (code "104") (name "Net-(U4-I{slash}O_5)") (class "Default")
      (node (ref "R3") (pin "1") (pinfunction "1_1") (pintype "passive"))
      (node (ref "U4") (pin "17") (pinfunction "I/O_5_17") (pintype "passive"))
    )
    (net (code "105") (name "Net-(U4-I{slash}O_6)") (class "Default")
      (node (ref "R2") (pin "1") (pinfunction "1_1") (pintype "passive"))
      (node (ref "U4") (pin "18") (pinfunction "I/O_6_18") (pintype "passive"))
    )
    (net (code "106") (name "Net-(U4-O_1)") (class "Default")
      (node (ref "U4") (pin "12") (pinfunction "O_1_12") (pintype "passive"))
      (node (ref "U5") (pin "1") (pinfunction "I_1_1") (pintype "passive"))
    )
    (net (code "107") (name "Net-(U6-A2)") (class "Default")
      (node (ref "U6") (pin "2") (pinfunction "Y1_2") (pintype "passive"))
      (node (ref "U6") (pin "3") (pinfunction "A2_3") (pintype "passive"))
    )
    (net (code "108") (name "VCC") (class "Default")
      (node (ref "C1") (pin "1") (pinfunction "1_1") (pintype "passive"))
      (node (ref "C12") (pin "1") (pinfunction "+_1") (pintype "passive"))
      (node (ref "C13") (pin "1") (pinfunction "+_1") (pintype "passive"))
      (node (ref "C14") (pin "1") (pinfunction "+_1") (pintype "passive"))
      (node (ref "C2") (pin "1") (pinfunction "1_1") (pintype "passive"))
      (node (ref "C3") (pin "1") (pinfunction "1_1") (pintype "passive"))
      (node (ref "C4") (pin "1") (pinfunction "1_1") (pintype "passive"))
      (node (ref "C5") (pin "1") (pinfunction "1_1") (pintype "passive"))
      (node (ref "C6") (pin "1") (pinfunction "1_1") (pintype "passive"))
      (node (ref "C7") (pin "1") (pinfunction "1_1") (pintype "passive"))
      (node (ref "U1") (pin "43") (pinfunction "VDD_43") (pintype "passive"))
      (node (ref "U1") (pin "9") (pinfunction "VDD_9") (pintype "passive"))
      (node (ref "U2") (pin "43") (pinfunction "VDD_43") (pintype "passive"))
      (node (ref "U2") (pin "9") (pinfunction "VDD_9") (pintype "passive"))
      (node (ref "U3") (pin "43") (pinfunction "VDD_43") (pintype "passive"))
      (node (ref "U3") (pin "9") (pinfunction "VDD_9") (pintype "passive"))
      (node (ref "U4") (pin "20") (pinfunction "VCC_20") (pintype "passive"))
      (node (ref "U5") (pin "20") (pinfunction "VCC_20") (pintype "passive"))
      (node (ref "U6") (pin "14") (pinfunction "VCC_14") (pintype "passive"))
    )
    (net (code "109") (name "unconnected-(U3-nIORQ-Pad59)") (class "Default")
      (node (ref "U3") (pin "59") (pinfunction "nIORQ_59") (pintype "passive+no_connect"))
    )
    (net (code "110") (name "unconnected-(U3-nRMCS-Pad60)") (class "Default")
      (node (ref "U3") (pin "60") (pinfunction "nRMCS_60") (pintype "passive+no_connect"))
    )
    (net (code "111") (name "unconnected-(U3-nSDAK-Pad49)") (class "Default")
      (node (ref "U3") (pin "49") (pinfunction "nSDAK_49") (pintype "passive+no_connect"))
    )
    (net (code "112") (name "unconnected-(U3-nSIRQ-Pad57)") (class "Default")
      (node (ref "U3") (pin "57") (pinfunction "nSIRQ_57") (pintype "passive+no_connect"))
    )
    (net (code "113") (name "unconnected-(U3-nVDAK-Pad50)") (class "Default")
      (node (ref "U3") (pin "50") (pinfunction "nVDAK_50") (pintype "passive+no_connect"))
    )
    (net (code "114") (name "unconnected-(U3-nVIDW-Pad51)") (class "Default")
      (node (ref "U3") (pin "51") (pinfunction "nVIDW_51") (pintype "passive+no_connect"))
    )
    (net (code "115") (name "unconnected-(U3-phi1-Pad66)") (class "Default")
      (node (ref "U3") (pin "66") (pinfunction "phi1_66") (pintype "passive+no_connect"))
    )
    (net (code "116") (name "unconnected-(U3-phi2-Pad65)") (class "Default")
      (node (ref "U3") (pin "65") (pinfunction "phi2_65") (pintype "passive+no_connect"))
    )
    (net (code "117") (name "unconnected-(U4-I_6-Pad6)") (class "Default")
      (node (ref "U4") (pin "6") (pinfunction "I_6_6") (pintype "passive+no_connect"))
    )
    (net (code "118") (name "unconnected-(U4-I_7-Pad7)") (class "Default")
      (node (ref "U4") (pin "7") (pinfunction "I_7_7") (pintype "passive+no_connect"))
    )
    (net (code "119") (name "unconnected-(U4-I_8-Pad8)") (class "Default")
      (node (ref "U4") (pin "8") (pinfunction "I_8_8") (pintype "passive+no_connect"))
    )
    (net (code "120") (name "unconnected-(U4-I_9-Pad9)") (class "Default")
      (node (ref "U4") (pin "9") (pinfunction "I_9_9") (pintype "passive+no_connect"))
    )
    (net (code "121") (name "unconnected-(U4-I_10-Pad11)") (class "Default")
      (node (ref "U4") (pin "11") (pinfunction "I_10_11") (pintype "passive+no_connect"))
    )
    (net (code "122") (name "unconnected-(U4-I{slash}O_2-Pad14)") (class "Default")
      (node (ref "U4") (pin "14") (pinfunction "I/O_2_14") (pintype "passive+no_connect"))
    )
    (net (code "123") (name "unconnected-(U4-O_2-Pad19)") (class "Default")
      (node (ref "U4") (pin "19") (pinfunction "O_2_19") (pintype "passive+no_connect"))
    )
    (net (code "124") (name "unconnected-(U5-I_10-Pad11)") (class "Default")
      (node (ref "U5") (pin "11") (pinfunction "I_10_11") (pintype "passive+no_connect"))
    )
    (net (code "125") (name "unconnected-(U5-I{slash}O_2-Pad14)") (class "Default")
      (node (ref "U5") (pin "14") (pinfunction "I/O_2_14") (pintype "passive+no_connect"))
    )
    (net (code "126") (name "unconnected-(U6-Y3-Pad6)") (class "Default")
      (node (ref "U6") (pin "6") (pinfunction "Y3_6") (pintype "passive+no_connect"))
    )
    (net (code "127") (name "unconnected-(U6-Y4-Pad8)") (class "Default")
      (node (ref "U6") (pin "8") (pinfunction "Y4_8") (pintype "passive+no_connect"))
    )
    (net (code "128") (name "unconnected-(U6-Y5-Pad10)") (class "Default")
      (node (ref "U6") (pin "10") (pinfunction "Y5_10") (pintype "passive+no_connect"))
    )
    (net (code "129") (name "unconnected-(U6-Y6-Pad12)") (class "Default")
      (node (ref "U6") (pin "12") (pinfunction "Y6_12") (pintype "passive+no_connect"))
    )
  )
)
